# DAQ_IO.net
KiCad netlist of a schematic drawn in Altium Designer
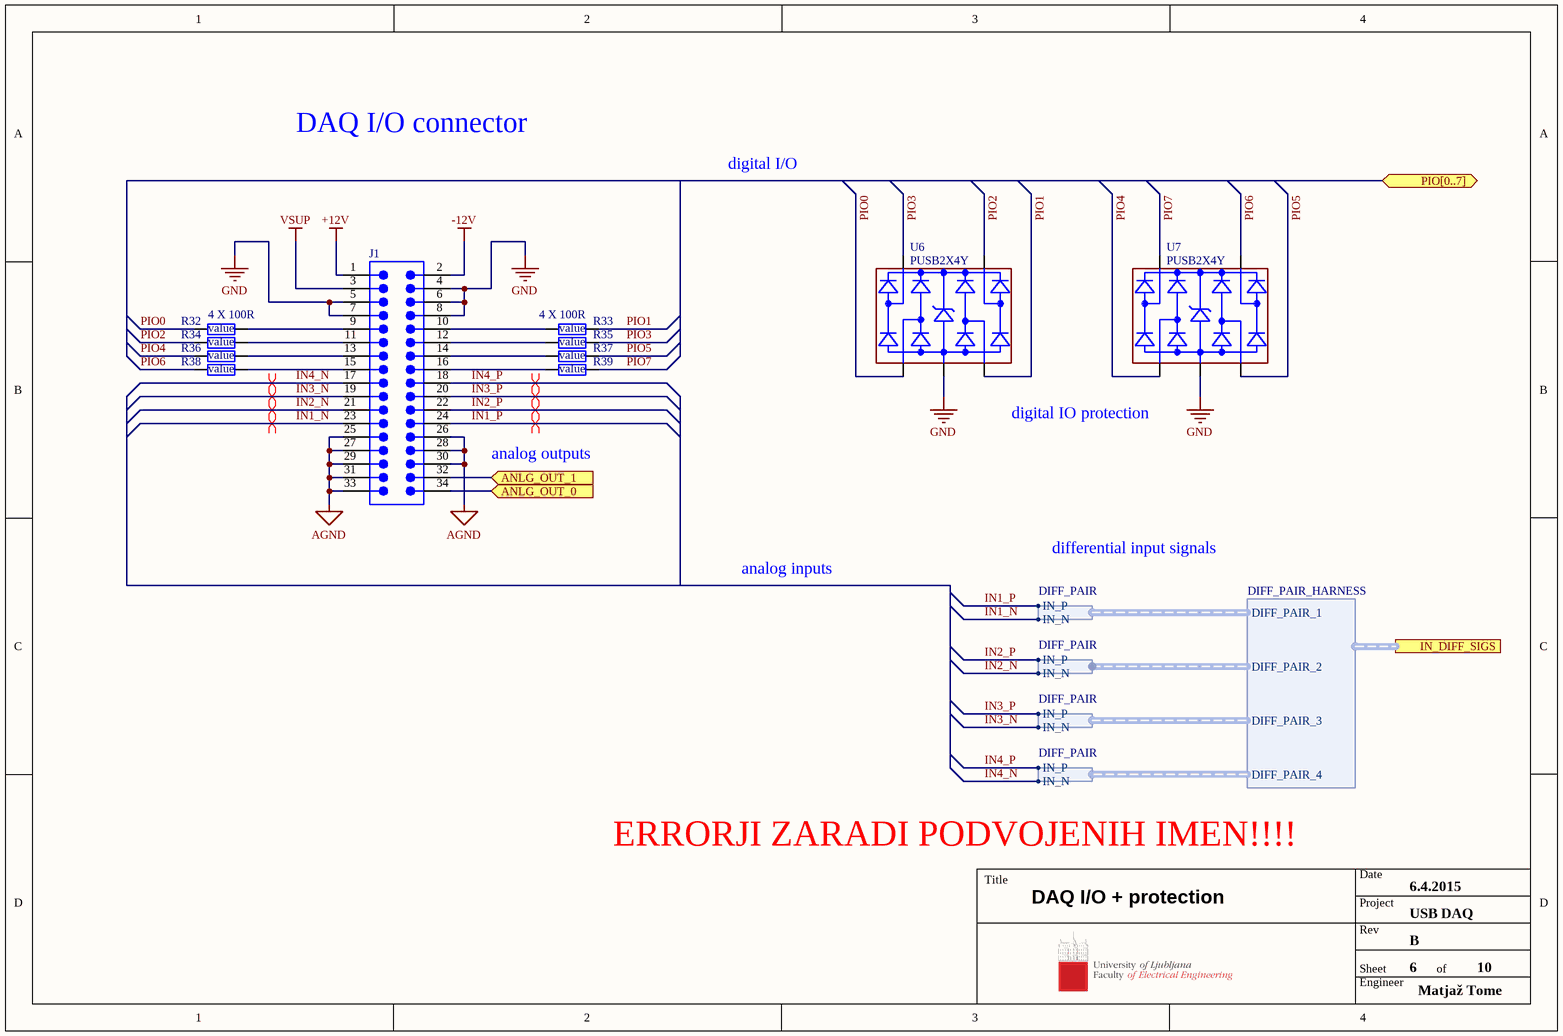
[diagram p0: DAQ_IO.SchDoc]

(export (version "E")
  (design (tool "Eeschema 10.0.6"))
  (components
    (comp (ref "J1")
      (value "2X17")
      (footprint "IDC34R")
      (description "Pin Header, Right Angle, Wire-to-Board, 2.54 mm, 2 Rows, 34 Contacts, Through Hole Right Angle")
      (fields (field (name "MANUFACTURER") "Harting"))
      (libsource (lib "DAQ") (part "09 18 534 7323"))
    )
    (comp (ref "R32")
      (value "value")
      (footprint "R_0603")
      (description "Generic resistor")
      (fields (field (name "Comment") "comment"))
      (libsource (lib "DAQ") (part "Resistor"))
    )
    (comp (ref "R33")
      (value "value")
      (footprint "R_0603")
      (description "Generic resistor")
      (fields (field (name "Comment") "comment"))
      (libsource (lib "DAQ") (part "Resistor"))
    )
    (comp (ref "R34")
      (value "value")
      (footprint "R_0603")
      (description "Generic resistor")
      (fields (field (name "Comment") "comment"))
      (libsource (lib "DAQ") (part "Resistor"))
    )
    (comp (ref "R35")
      (value "value")
      (footprint "R_0603")
      (description "Generic resistor")
      (fields (field (name "Comment") "comment"))
      (libsource (lib "DAQ") (part "Resistor"))
    )
    (comp (ref "R36")
      (value "value")
      (footprint "R_0603")
      (description "Generic resistor")
      (fields (field (name "Comment") "comment"))
      (libsource (lib "DAQ") (part "Resistor"))
    )
    (comp (ref "R37")
      (value "value")
      (footprint "R_0603")
      (description "Generic resistor")
      (fields (field (name "Comment") "comment"))
      (libsource (lib "DAQ") (part "Resistor"))
    )
    (comp (ref "R38")
      (value "value")
      (footprint "R_0603")
      (description "Generic resistor")
      (fields (field (name "Comment") "comment"))
      (libsource (lib "DAQ") (part "Resistor"))
    )
    (comp (ref "R39")
      (value "value")
      (footprint "R_0603")
      (description "Generic resistor")
      (fields (field (name "Comment") "comment"))
      (libsource (lib "DAQ") (part "Resistor"))
    )
    (comp (ref "U6")
      (value "PUSB2X4Y")
      (footprint "SOT363")
      (description "ESD Protection Device, 3.8 V, SC-88, 6 Pins, PUSB2 Series")
      (fields (field (name "MANUFACTURER") "Multicomp"))
      (libsource (lib "DAQ") (part "PUSB2X4Y"))
    )
    (comp (ref "U7")
      (value "PUSB2X4Y")
      (footprint "SOT363")
      (description "ESD Protection Device, 3.8 V, SC-88, 6 Pins, PUSB2 Series")
      (fields (field (name "MANUFACTURER") "Multicomp"))
      (libsource (lib "DAQ") (part "PUSB2X4Y"))
    )
  )
  (nets
    (net (code "3") (name "+12V") (class "Default")
      (node (ref "J1") (pin "1") (pinfunction "1_1") (pintype "passive"))
    )
    (net (code "4") (name "-12V") (class "Default")
      (node (ref "J1") (pin "2") (pinfunction "2_2") (pintype "passive"))
    )
    (net (code "5") (name "/ANLG_OUT_0") (class "Default")
      (node (ref "J1") (pin "34") (pinfunction "34_34") (pintype "passive"))
    )
    (net (code "6") (name "/ANLG_OUT_1") (class "Default")
      (node (ref "J1") (pin "32") (pinfunction "32_32") (pintype "passive"))
    )
    (net (code "7") (name "/IN1_N") (class "Default")
      (node (ref "J1") (pin "23") (pinfunction "23_23") (pintype "passive"))
    )
    (net (code "8") (name "/IN1_P") (class "Default")
      (node (ref "J1") (pin "24") (pinfunction "24_24") (pintype "passive"))
    )
    (net (code "9") (name "/IN2_N") (class "Default")
      (node (ref "J1") (pin "21") (pinfunction "21_21") (pintype "passive"))
    )
    (net (code "10") (name "/IN2_P") (class "Default")
      (node (ref "J1") (pin "22") (pinfunction "22_22") (pintype "passive"))
    )
    (net (code "11") (name "/IN3_N") (class "Default")
      (node (ref "J1") (pin "19") (pinfunction "19_19") (pintype "passive"))
    )
    (net (code "12") (name "/IN3_P") (class "Default")
      (node (ref "J1") (pin "20") (pinfunction "20_20") (pintype "passive"))
    )
    (net (code "13") (name "/IN4_N") (class "Default")
      (node (ref "J1") (pin "17") (pinfunction "17_17") (pintype "passive"))
    )
    (net (code "14") (name "/IN4_P") (class "Default")
      (node (ref "J1") (pin "18") (pinfunction "18_18") (pintype "passive"))
    )
    (net (code "15") (name "/PIO0") (class "Default")
      (node (ref "R32") (pin "1") (pintype "passive"))
      (node (ref "U6") (pin "1") (pinfunction "1_1") (pintype "passive"))
    )
    (net (code "16") (name "/PIO1") (class "Default")
      (node (ref "R33") (pin "2") (pintype "passive"))
      (node (ref "U6") (pin "3") (pinfunction "3_3") (pintype "passive"))
    )
    (net (code "17") (name "/PIO2") (class "Default")
      (node (ref "R34") (pin "1") (pintype "passive"))
      (node (ref "U6") (pin "4") (pinfunction "4_4") (pintype "passive"))
    )
    (net (code "18") (name "/PIO3") (class "Default")
      (node (ref "R35") (pin "2") (pintype "passive"))
      (node (ref "U6") (pin "6") (pinfunction "6_6") (pintype "passive"))
    )
    (net (code "19") (name "/PIO4") (class "Default")
      (node (ref "R36") (pin "1") (pintype "passive"))
      (node (ref "U7") (pin "1") (pinfunction "1_1") (pintype "passive"))
    )
    (net (code "20") (name "/PIO5") (class "Default")
      (node (ref "R37") (pin "2") (pintype "passive"))
      (node (ref "U7") (pin "3") (pinfunction "3_3") (pintype "passive"))
    )
    (net (code "21") (name "/PIO6") (class "Default")
      (node (ref "R38") (pin "1") (pintype "passive"))
      (node (ref "U7") (pin "4") (pinfunction "4_4") (pintype "passive"))
    )
    (net (code "22") (name "/PIO7") (class "Default")
      (node (ref "R39") (pin "2") (pintype "passive"))
      (node (ref "U7") (pin "6") (pinfunction "6_6") (pintype "passive"))
    )
    (net (code "26") (name "AGND") (class "Default")
      (node (ref "J1") (pin "25") (pinfunction "25_25") (pintype "passive"))
      (node (ref "J1") (pin "26") (pinfunction "26_26") (pintype "passive"))
      (node (ref "J1") (pin "27") (pinfunction "27_27") (pintype "passive"))
      (node (ref "J1") (pin "28") (pinfunction "28_28") (pintype "passive"))
      (node (ref "J1") (pin "29") (pinfunction "29_29") (pintype "passive"))
      (node (ref "J1") (pin "30") (pinfunction "30_30") (pintype "passive"))
      (node (ref "J1") (pin "31") (pinfunction "31_31") (pintype "passive"))
      (node (ref "J1") (pin "33") (pinfunction "33_33") (pintype "passive"))
    )
    (net (code "27") (name "GND") (class "Default")
      (node (ref "J1") (pin "4") (pinfunction "4_4") (pintype "passive"))
      (node (ref "J1") (pin "5") (pinfunction "5_5") (pintype "passive"))
      (node (ref "J1") (pin "6") (pinfunction "6_6") (pintype "passive"))
      (node (ref "J1") (pin "7") (pinfunction "7_7") (pintype "passive"))
      (node (ref "J1") (pin "8") (pinfunction "8_8") (pintype "passive"))
      (node (ref "U6") (pin "2") (pinfunction "2_2") (pintype "passive"))
      (node (ref "U7") (pin "2") (pinfunction "2_2") (pintype "passive"))
    )
    (net (code "28") (name "Net-(J1-Pad9)") (class "Default")
      (node (ref "J1") (pin "9") (pinfunction "9_9") (pintype "passive"))
      (node (ref "R32") (pin "2") (pintype "passive"))
    )
    (net (code "29") (name "Net-(J1-Pad10)") (class "Default")
      (node (ref "J1") (pin "10") (pinfunction "10_10") (pintype "passive"))
      (node (ref "R33") (pin "1") (pintype "passive"))
    )
    (net (code "30") (name "Net-(J1-Pad11)") (class "Default")
      (node (ref "J1") (pin "11") (pinfunction "11_11") (pintype "passive"))
      (node (ref "R34") (pin "2") (pintype "passive"))
    )
    (net (code "31") (name "Net-(J1-Pad12)") (class "Default")
      (node (ref "J1") (pin "12") (pinfunction "12_12") (pintype "passive"))
      (node (ref "R35") (pin "1") (pintype "passive"))
    )
    (net (code "32") (name "Net-(J1-Pad13)") (class "Default")
      (node (ref "J1") (pin "13") (pinfunction "13_13") (pintype "passive"))
      (node (ref "R36") (pin "2") (pintype "passive"))
    )
    (net (code "33") (name "Net-(J1-Pad14)") (class "Default")
      (node (ref "J1") (pin "14") (pinfunction "14_14") (pintype "passive"))
      (node (ref "R37") (pin "1") (pintype "passive"))
    )
    (net (code "34") (name "Net-(J1-Pad15)") (class "Default")
      (node (ref "J1") (pin "15") (pinfunction "15_15") (pintype "passive"))
      (node (ref "R38") (pin "2") (pintype "passive"))
    )
    (net (code "35") (name "Net-(J1-Pad16)") (class "Default")
      (node (ref "J1") (pin "16") (pinfunction "16_16") (pintype "passive"))
      (node (ref "R39") (pin "1") (pintype "passive"))
    )
    (net (code "36") (name "VSUP") (class "Default")
      (node (ref "J1") (pin "3") (pinfunction "3_3") (pintype "passive"))
    )
  )
)
